# HalfMegCoCo_ZIP.net
KiCad netlist of a schematic drawn in EAGLE
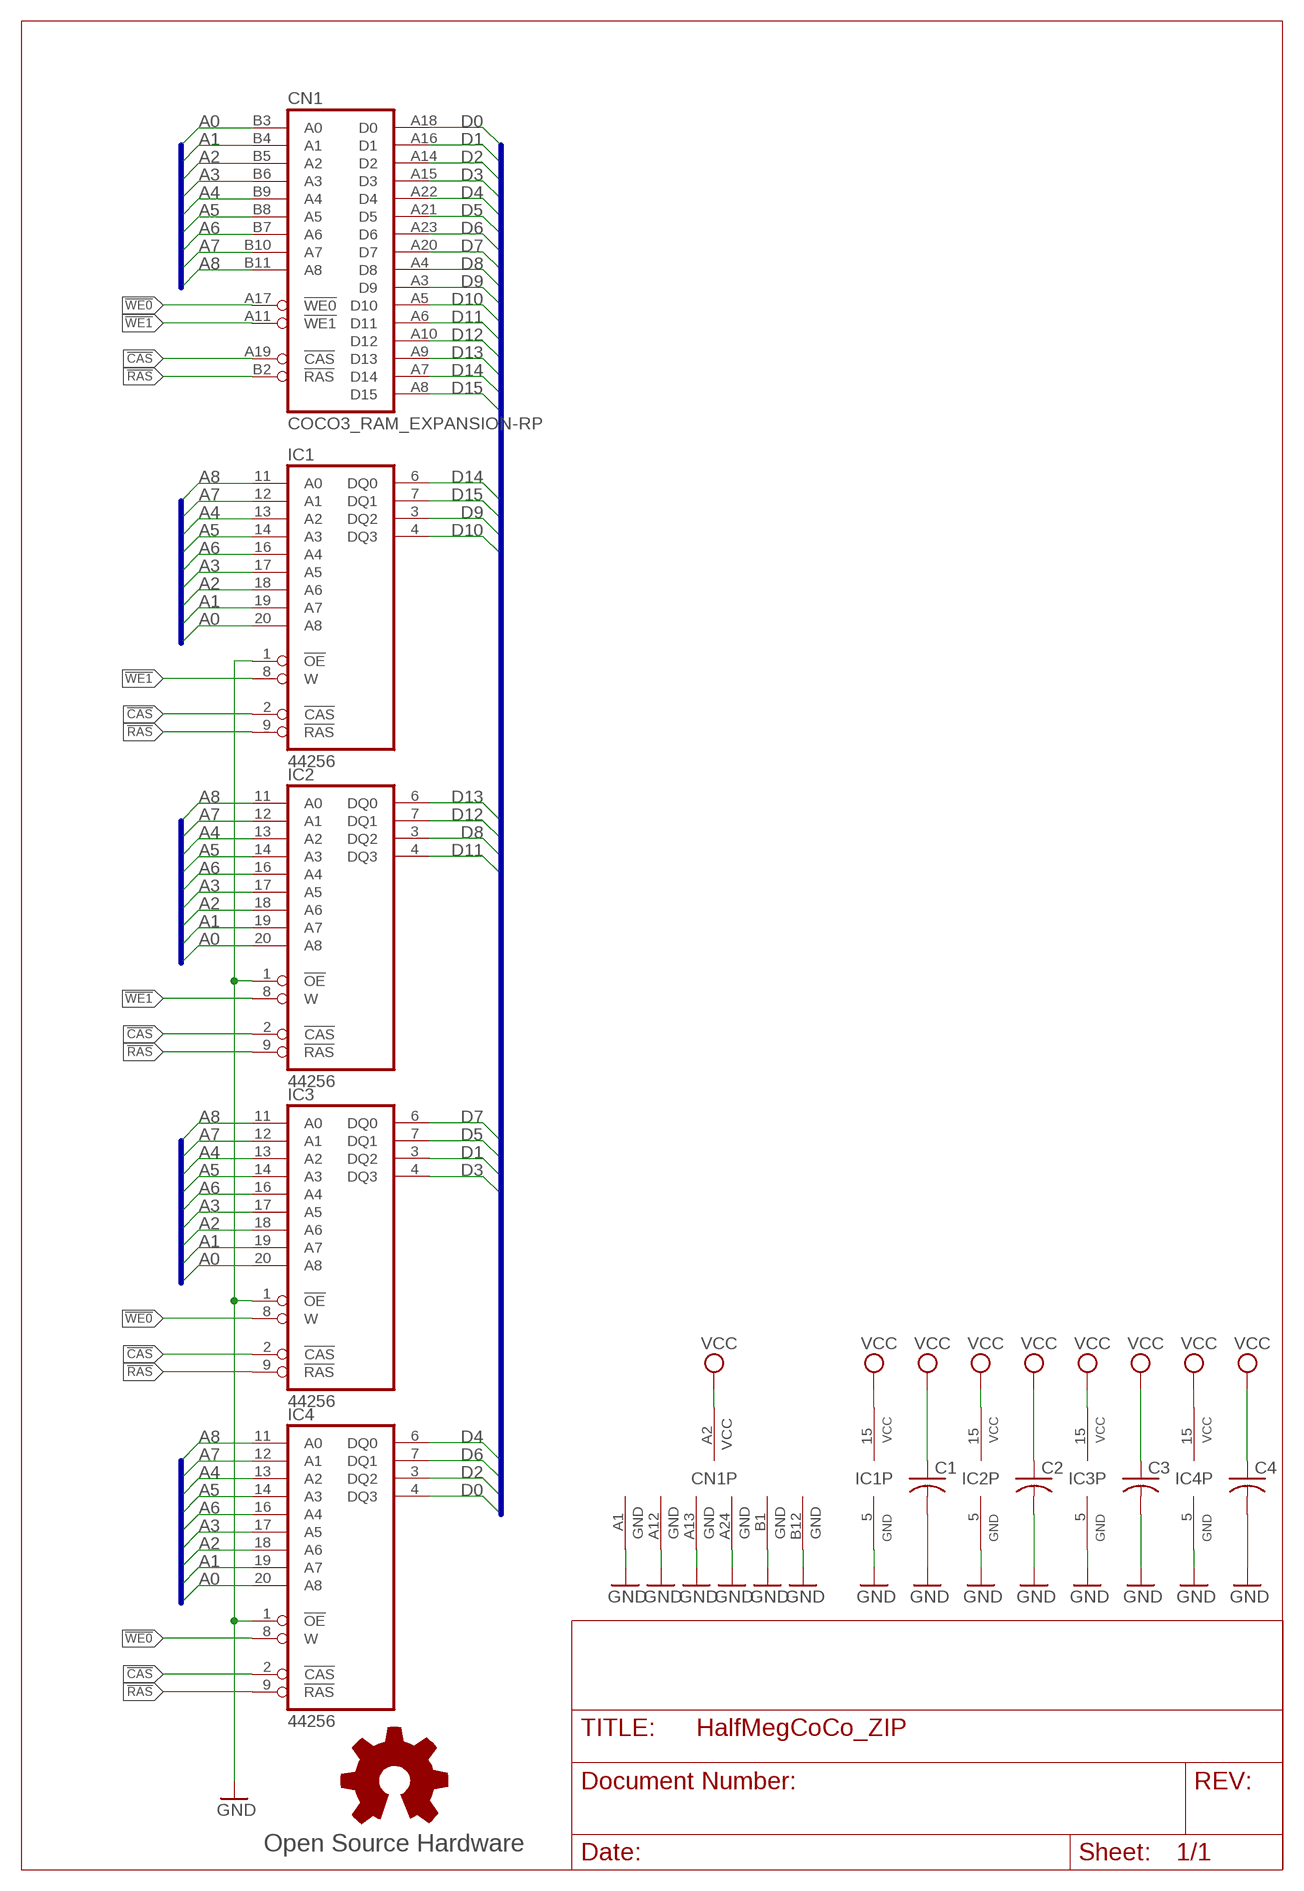
[diagram p0: schematic, sheet 1]

(export (version "E")
  (design (tool "Eeschema 10.0.6"))
  (components
    (comp (ref "C1")
      (value "C-US025-025X050")
      (footprint "eagle-import:C025-025X050")
      (libsource (lib "eagle-import") (part "C-US025-025X050"))
    )
    (comp (ref "C2")
      (value "C-US025-025X050")
      (footprint "eagle-import:C025-025X050")
      (libsource (lib "eagle-import") (part "C-US025-025X050"))
    )
    (comp (ref "C3")
      (value "C-US025-025X050")
      (footprint "eagle-import:C025-025X050")
      (libsource (lib "eagle-import") (part "C-US025-025X050"))
    )
    (comp (ref "C4")
      (value "C-US025-025X050")
      (footprint "eagle-import:C025-025X050")
      (libsource (lib "eagle-import") (part "C-US025-025X050"))
    )
    (comp (ref "CN1")
      (value "COCO3_RAM_EXPANSION-RP")
      (footprint "eagle-import:RAM_EXPANSION-RP")
      (libsource (lib "eagle-import") (part "COCO3_RAM_EXPANSION-RP"))
    )
    (comp (ref "GOLD_ORB_SM1")
      (value "Open Source Hardware")
      (footprint "eagle-import:OSHW_8MM")
      (libsource (lib "eagle-import") (part "OSHWLOGOLOGO8MM"))
    )
    (comp (ref "IC1")
      (value "44256")
      (footprint "eagle-import:ZIP20")
      (libsource (lib "eagle-import") (part "44256L"))
    )
    (comp (ref "IC2")
      (value "44256")
      (footprint "eagle-import:ZIP20")
      (libsource (lib "eagle-import") (part "44256L"))
    )
    (comp (ref "IC3")
      (value "44256")
      (footprint "eagle-import:ZIP20")
      (libsource (lib "eagle-import") (part "44256L"))
    )
    (comp (ref "IC4")
      (value "44256")
      (footprint "eagle-import:ZIP20")
      (libsource (lib "eagle-import") (part "44256L"))
    )
  )
  (nets
    (net (code "1") (name "/A0") (class "Default")
      (node (ref "CN1") (pin "B3") (pinfunction "A0_B3") (pintype "output"))
      (node (ref "IC1") (pin "20") (pinfunction "A8_20") (pintype "input"))
      (node (ref "IC2") (pin "20") (pinfunction "A8_20") (pintype "input"))
      (node (ref "IC3") (pin "20") (pinfunction "A8_20") (pintype "input"))
      (node (ref "IC4") (pin "20") (pinfunction "A8_20") (pintype "input"))
    )
    (net (code "2") (name "/A1") (class "Default")
      (node (ref "CN1") (pin "B4") (pinfunction "A1_B4") (pintype "output"))
      (node (ref "IC1") (pin "19") (pinfunction "A7_19") (pintype "input"))
      (node (ref "IC2") (pin "19") (pinfunction "A7_19") (pintype "input"))
      (node (ref "IC3") (pin "19") (pinfunction "A7_19") (pintype "input"))
      (node (ref "IC4") (pin "19") (pinfunction "A7_19") (pintype "input"))
    )
    (net (code "3") (name "/A2") (class "Default")
      (node (ref "CN1") (pin "B5") (pinfunction "A2_B5") (pintype "output"))
      (node (ref "IC1") (pin "18") (pinfunction "A6_18") (pintype "input"))
      (node (ref "IC2") (pin "18") (pinfunction "A6_18") (pintype "input"))
      (node (ref "IC3") (pin "18") (pinfunction "A6_18") (pintype "input"))
      (node (ref "IC4") (pin "18") (pinfunction "A6_18") (pintype "input"))
    )
    (net (code "4") (name "/A3") (class "Default")
      (node (ref "CN1") (pin "B6") (pinfunction "A3_B6") (pintype "output"))
      (node (ref "IC1") (pin "17") (pinfunction "A5_17") (pintype "input"))
      (node (ref "IC2") (pin "17") (pinfunction "A5_17") (pintype "input"))
      (node (ref "IC3") (pin "17") (pinfunction "A5_17") (pintype "input"))
      (node (ref "IC4") (pin "17") (pinfunction "A5_17") (pintype "input"))
    )
    (net (code "5") (name "/A4") (class "Default")
      (node (ref "CN1") (pin "B9") (pinfunction "A4_B9") (pintype "output"))
      (node (ref "IC1") (pin "13") (pinfunction "A2_13") (pintype "input"))
      (node (ref "IC2") (pin "13") (pinfunction "A2_13") (pintype "input"))
      (node (ref "IC3") (pin "13") (pinfunction "A2_13") (pintype "input"))
      (node (ref "IC4") (pin "13") (pinfunction "A2_13") (pintype "input"))
    )
    (net (code "6") (name "/A5") (class "Default")
      (node (ref "CN1") (pin "B8") (pinfunction "A5_B8") (pintype "output"))
      (node (ref "IC1") (pin "14") (pinfunction "A3_14") (pintype "input"))
      (node (ref "IC2") (pin "14") (pinfunction "A3_14") (pintype "input"))
      (node (ref "IC3") (pin "14") (pinfunction "A3_14") (pintype "input"))
      (node (ref "IC4") (pin "14") (pinfunction "A3_14") (pintype "input"))
    )
    (net (code "7") (name "/A6") (class "Default")
      (node (ref "CN1") (pin "B7") (pinfunction "A6_B7") (pintype "output"))
      (node (ref "IC1") (pin "16") (pinfunction "A4_16") (pintype "input"))
      (node (ref "IC2") (pin "16") (pinfunction "A4_16") (pintype "input"))
      (node (ref "IC3") (pin "16") (pinfunction "A4_16") (pintype "input"))
      (node (ref "IC4") (pin "16") (pinfunction "A4_16") (pintype "input"))
    )
    (net (code "8") (name "/A7") (class "Default")
      (node (ref "CN1") (pin "B10") (pinfunction "A7_B10") (pintype "output"))
      (node (ref "IC1") (pin "12") (pinfunction "A1_12") (pintype "input"))
      (node (ref "IC2") (pin "12") (pinfunction "A1_12") (pintype "input"))
      (node (ref "IC3") (pin "12") (pinfunction "A1_12") (pintype "input"))
      (node (ref "IC4") (pin "12") (pinfunction "A1_12") (pintype "input"))
    )
    (net (code "9") (name "/A8") (class "Default")
      (node (ref "CN1") (pin "B11") (pinfunction "A8_B11") (pintype "output"))
      (node (ref "IC1") (pin "11") (pinfunction "A0_11") (pintype "input"))
      (node (ref "IC2") (pin "11") (pinfunction "A0_11") (pintype "input"))
      (node (ref "IC3") (pin "11") (pinfunction "A0_11") (pintype "input"))
      (node (ref "IC4") (pin "11") (pinfunction "A0_11") (pintype "input"))
    )
    (net (code "10") (name "/D0") (class "Default")
      (node (ref "CN1") (pin "A18") (pinfunction "D0_A18") (pintype "bidirectional"))
      (node (ref "IC4") (pin "4") (pinfunction "DQ3_4") (pintype "bidirectional"))
    )
    (net (code "11") (name "/D1") (class "Default")
      (node (ref "CN1") (pin "A16") (pinfunction "D1_A16") (pintype "bidirectional"))
      (node (ref "IC3") (pin "3") (pinfunction "DQ2_3") (pintype "bidirectional"))
    )
    (net (code "12") (name "/D2") (class "Default")
      (node (ref "CN1") (pin "A14") (pinfunction "D2_A14") (pintype "bidirectional"))
      (node (ref "IC4") (pin "3") (pinfunction "DQ2_3") (pintype "bidirectional"))
    )
    (net (code "13") (name "/D3") (class "Default")
      (node (ref "CN1") (pin "A15") (pinfunction "D3_A15") (pintype "bidirectional"))
      (node (ref "IC3") (pin "4") (pinfunction "DQ3_4") (pintype "bidirectional"))
    )
    (net (code "14") (name "/D4") (class "Default")
      (node (ref "CN1") (pin "A22") (pinfunction "D4_A22") (pintype "bidirectional"))
      (node (ref "IC4") (pin "6") (pinfunction "DQ0_6") (pintype "bidirectional"))
    )
    (net (code "15") (name "/D5") (class "Default")
      (node (ref "CN1") (pin "A21") (pinfunction "D5_A21") (pintype "bidirectional"))
      (node (ref "IC3") (pin "7") (pinfunction "DQ1_7") (pintype "bidirectional"))
    )
    (net (code "16") (name "/D6") (class "Default")
      (node (ref "CN1") (pin "A23") (pinfunction "D6_A23") (pintype "bidirectional"))
      (node (ref "IC4") (pin "7") (pinfunction "DQ1_7") (pintype "bidirectional"))
    )
    (net (code "17") (name "/D7") (class "Default")
      (node (ref "CN1") (pin "A20") (pinfunction "D7_A20") (pintype "bidirectional"))
      (node (ref "IC3") (pin "6") (pinfunction "DQ0_6") (pintype "bidirectional"))
    )
    (net (code "18") (name "/D8") (class "Default")
      (node (ref "CN1") (pin "A4") (pinfunction "D8_A4") (pintype "bidirectional"))
      (node (ref "IC2") (pin "3") (pinfunction "DQ2_3") (pintype "bidirectional"))
    )
    (net (code "19") (name "/D9") (class "Default")
      (node (ref "CN1") (pin "A3") (pinfunction "D9_A3") (pintype "bidirectional"))
      (node (ref "IC1") (pin "3") (pinfunction "DQ2_3") (pintype "bidirectional"))
    )
    (net (code "20") (name "/D10") (class "Default")
      (node (ref "CN1") (pin "A5") (pinfunction "D10_A5") (pintype "bidirectional"))
      (node (ref "IC1") (pin "4") (pinfunction "DQ3_4") (pintype "bidirectional"))
    )
    (net (code "21") (name "/D11") (class "Default")
      (node (ref "CN1") (pin "A6") (pinfunction "D11_A6") (pintype "bidirectional"))
      (node (ref "IC2") (pin "4") (pinfunction "DQ3_4") (pintype "bidirectional"))
    )
    (net (code "22") (name "/D12") (class "Default")
      (node (ref "CN1") (pin "A10") (pinfunction "D12_A10") (pintype "bidirectional"))
      (node (ref "IC2") (pin "7") (pinfunction "DQ1_7") (pintype "bidirectional"))
    )
    (net (code "23") (name "/D13") (class "Default")
      (node (ref "CN1") (pin "A9") (pinfunction "D13_A9") (pintype "bidirectional"))
      (node (ref "IC2") (pin "6") (pinfunction "DQ0_6") (pintype "bidirectional"))
    )
    (net (code "24") (name "/D14") (class "Default")
      (node (ref "CN1") (pin "A7") (pinfunction "D14_A7") (pintype "bidirectional"))
      (node (ref "IC1") (pin "6") (pinfunction "DQ0_6") (pintype "bidirectional"))
    )
    (net (code "25") (name "/D15") (class "Default")
      (node (ref "CN1") (pin "A8") (pinfunction "D15_A8") (pintype "bidirectional"))
      (node (ref "IC1") (pin "7") (pinfunction "DQ1_7") (pintype "bidirectional"))
    )
    (net (code "26") (name "/~{CAS}") (class "Default")
      (node (ref "CN1") (pin "A19") (pinfunction "~{CAS}_A19") (pintype "output"))
      (node (ref "IC1") (pin "2") (pinfunction "~{CAS}_2") (pintype "input"))
      (node (ref "IC2") (pin "2") (pinfunction "~{CAS}_2") (pintype "input"))
      (node (ref "IC3") (pin "2") (pinfunction "~{CAS}_2") (pintype "input"))
      (node (ref "IC4") (pin "2") (pinfunction "~{CAS}_2") (pintype "input"))
    )
    (net (code "27") (name "/~{RAS}") (class "Default")
      (node (ref "CN1") (pin "B2") (pinfunction "~{RAS}_B2") (pintype "output"))
      (node (ref "IC1") (pin "9") (pinfunction "~{RAS}_9") (pintype "input"))
      (node (ref "IC2") (pin "9") (pinfunction "~{RAS}_9") (pintype "input"))
      (node (ref "IC3") (pin "9") (pinfunction "~{RAS}_9") (pintype "input"))
      (node (ref "IC4") (pin "9") (pinfunction "~{RAS}_9") (pintype "input"))
    )
    (net (code "28") (name "/~{WE0}") (class "Default")
      (node (ref "CN1") (pin "A17") (pinfunction "~{WE0}_A17") (pintype "output"))
      (node (ref "IC3") (pin "8") (pinfunction "W_8") (pintype "input"))
      (node (ref "IC4") (pin "8") (pinfunction "W_8") (pintype "input"))
    )
    (net (code "29") (name "/~{WE1}") (class "Default")
      (node (ref "CN1") (pin "A11") (pinfunction "~{WE1}_A11") (pintype "output"))
      (node (ref "IC1") (pin "8") (pinfunction "W_8") (pintype "input"))
      (node (ref "IC2") (pin "8") (pinfunction "W_8") (pintype "input"))
    )
    (net (code "30") (name "GND") (class "Default")
      (node (ref "C1") (pin "2") (pinfunction "2_2") (pintype "passive"))
      (node (ref "C2") (pin "2") (pinfunction "2_2") (pintype "passive"))
      (node (ref "C3") (pin "2") (pinfunction "2_2") (pintype "passive"))
      (node (ref "C4") (pin "2") (pinfunction "2_2") (pintype "passive"))
      (node (ref "CN1") (pin "A1") (pinfunction "GND_A1") (pintype "power_in"))
      (node (ref "CN1") (pin "A12") (pinfunction "GND_A12") (pintype "power_in"))
      (node (ref "CN1") (pin "A13") (pinfunction "GND_A13") (pintype "power_in"))
      (node (ref "CN1") (pin "A24") (pinfunction "GND_A24") (pintype "power_in"))
      (node (ref "CN1") (pin "B1") (pinfunction "GND_B1") (pintype "power_in"))
      (node (ref "CN1") (pin "B12") (pinfunction "GND_B12") (pintype "power_in"))
      (node (ref "IC1") (pin "1") (pinfunction "~{OE}_1") (pintype "input"))
      (node (ref "IC1") (pin "5") (pinfunction "GND_5") (pintype "power_in"))
      (node (ref "IC2") (pin "1") (pinfunction "~{OE}_1") (pintype "input"))
      (node (ref "IC2") (pin "5") (pinfunction "GND_5") (pintype "power_in"))
      (node (ref "IC3") (pin "1") (pinfunction "~{OE}_1") (pintype "input"))
      (node (ref "IC3") (pin "5") (pinfunction "GND_5") (pintype "power_in"))
      (node (ref "IC4") (pin "1") (pinfunction "~{OE}_1") (pintype "input"))
      (node (ref "IC4") (pin "5") (pinfunction "GND_5") (pintype "power_in"))
    )
    (net (code "31") (name "VCC") (class "Default")
      (node (ref "C1") (pin "1") (pinfunction "1_1") (pintype "passive"))
      (node (ref "C2") (pin "1") (pinfunction "1_1") (pintype "passive"))
      (node (ref "C3") (pin "1") (pinfunction "1_1") (pintype "passive"))
      (node (ref "C4") (pin "1") (pinfunction "1_1") (pintype "passive"))
      (node (ref "CN1") (pin "A2") (pinfunction "VCC_A2") (pintype "power_in"))
      (node (ref "IC1") (pin "15") (pinfunction "VCC_15") (pintype "power_in"))
      (node (ref "IC2") (pin "15") (pinfunction "VCC_15") (pintype "power_in"))
      (node (ref "IC3") (pin "15") (pinfunction "VCC_15") (pintype "power_in"))
      (node (ref "IC4") (pin "15") (pinfunction "VCC_15") (pintype "power_in"))
    )
  )
)
